# MTX_pic_piggyback_BRW_SOIC_V14.net
KiCad netlist of a schematic drawn in EAGLE
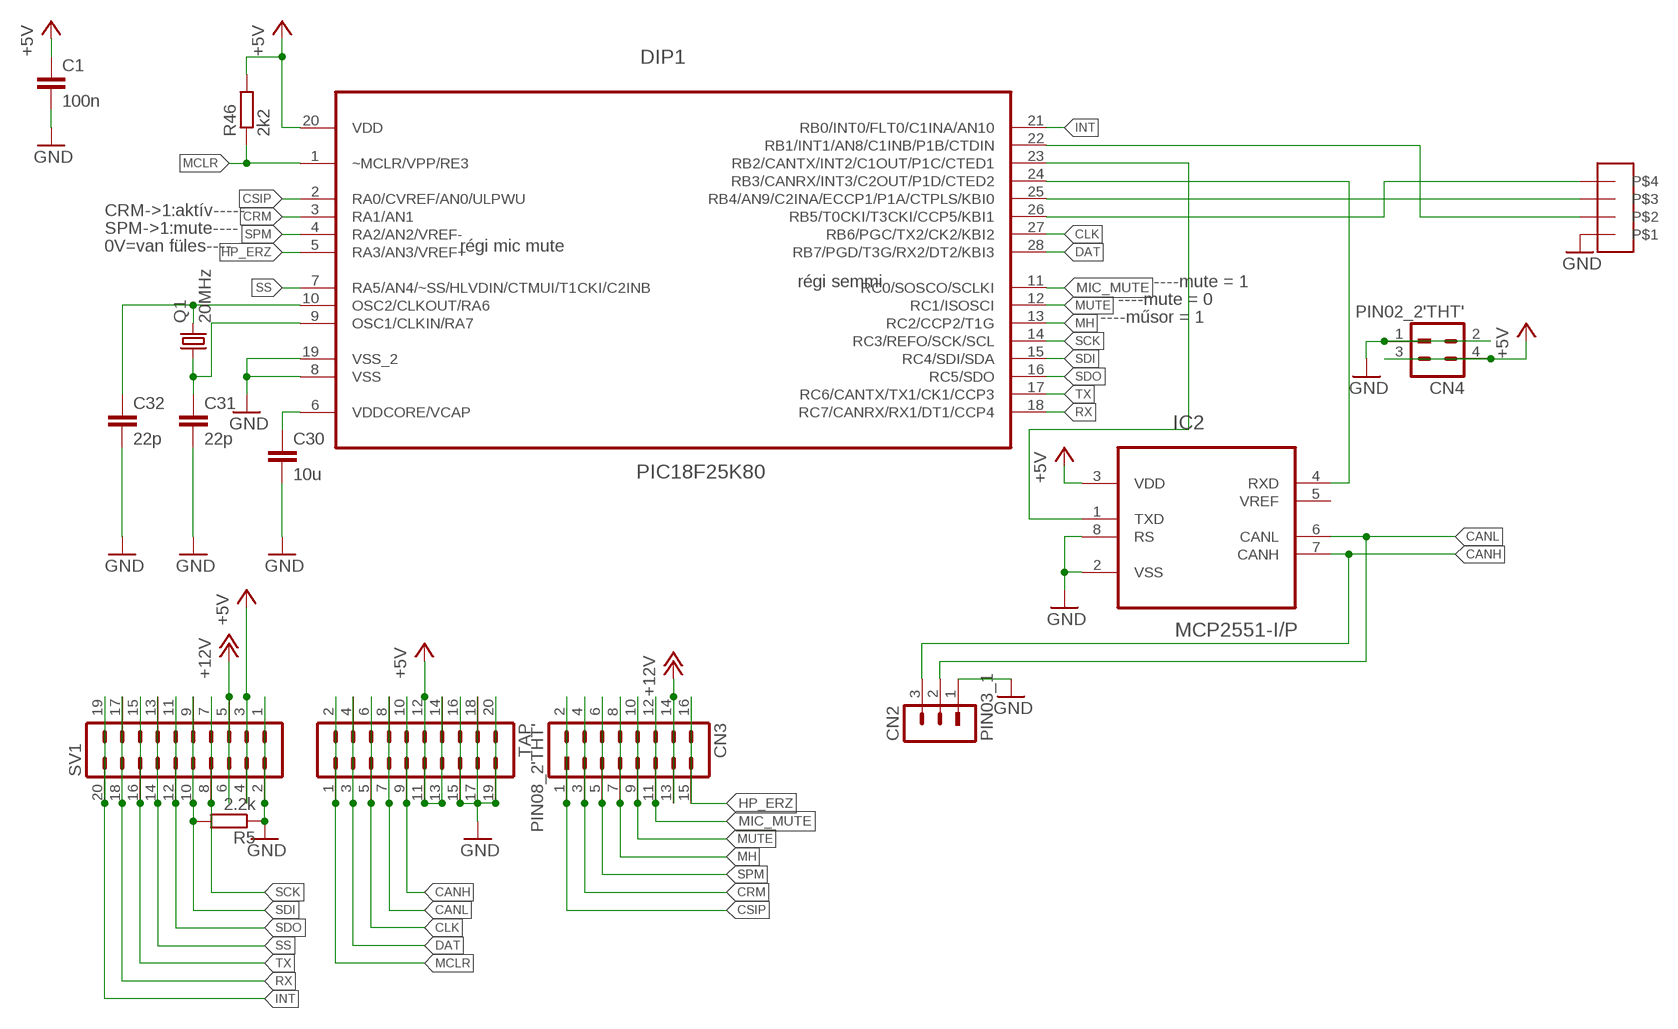
[diagram p0: schematic, sheet 1]

(export (version "E")
  (design (tool "Eeschema 10.0.6"))
  (components
    (comp (ref "C1")
      (value "100n")
      (footprint "eagle-import:C0805")
      (libsource (lib "eagle-import") (part "C-EUC0805"))
    )
    (comp (ref "C30")
      (value "10u")
      (footprint "eagle-import:C0805")
      (libsource (lib "eagle-import") (part "C-EUC0805"))
    )
    (comp (ref "C31")
      (value "22p")
      (footprint "eagle-import:C0805")
      (libsource (lib "eagle-import") (part "C-EUC0805"))
    )
    (comp (ref "C32")
      (value "22p")
      (footprint "eagle-import:C0805")
      (libsource (lib "eagle-import") (part "C-EUC0805"))
    )
    (comp (ref "CN2")
      (value "PIN03_1")
      (footprint "eagle-import:PIN03_1")
      (libsource (lib "eagle-import") (part "PIN03_1"))
    )
    (comp (ref "CN3")
      (value "PIN08_2'THT'")
      (footprint "eagle-import:PIN08_2")
      (libsource (lib "eagle-import") (part "PIN08_2'THT'"))
    )
    (comp (ref "CN4")
      (value "PIN02_2'THT'")
      (footprint "eagle-import:PIN02_2")
      (libsource (lib "eagle-import") (part "PIN02_2'THT'"))
    )
    (comp (ref "DIP1")
      (value "PIC18F25K80")
      (footprint "eagle-import:SOIC127P1030X265-28N")
      (libsource (lib "eagle-import") (part "PIC18F25K80"))
    )
    (comp (ref "IC2")
      (value "MCP2551-I/P")
      (footprint "eagle-import:DIP254P762X432-8")
      (libsource (lib "eagle-import") (part "MCP2551-I/P"))
    )
    (comp (ref "Q1")
      (value "20MHz")
      (footprint "eagle-import:XTAL_QS")
      (libsource (lib "eagle-import") (part "XTAL_2QS"))
    )
    (comp (ref "R5")
      (value "2.2k")
      (footprint "eagle-import:R0805")
      (libsource (lib "eagle-import") (part "R-EU_R0805"))
    )
    (comp (ref "R46")
      (value "2k2")
      (footprint "eagle-import:R0805")
      (libsource (lib "eagle-import") (part "R-EU_R0805"))
    )
    (comp (ref "SV1")
      (value "MA10-2")
      (footprint "eagle-import:MA10-2")
      (libsource (lib "eagle-import") (part "MA10-2"))
    )
    (comp (ref "TAP")
      (value "MA10-2")
      (footprint "eagle-import:MA10-2")
      (libsource (lib "eagle-import") (part "MA10-2"))
    )
    (comp (ref "U$1")
      (value "FEHER_TUS_4")
      (footprint "eagle-import:FEHER_TUS_4")
      (libsource (lib "eagle-import") (part "FEHER_TUS_4"))
    )
  )
  (nets
    (net (code "1") (name "+5V") (class "Default")
      (node (ref "C1") (pin "1") (pinfunction "1_1") (pintype "passive"))
      (node (ref "CN4") (pin "3") (pinfunction "3_3") (pintype "passive"))
      (node (ref "CN4") (pin "4") (pinfunction "4_4") (pintype "passive"))
      (node (ref "DIP1") (pin "20") (pinfunction "VDD_20") (pintype "power_in"))
      (node (ref "IC2") (pin "3") (pinfunction "VDD_3") (pintype "power_in"))
      (node (ref "R46") (pin "2") (pinfunction "2_2") (pintype "passive"))
      (node (ref "SV1") (pin "3") (pinfunction "3_3") (pintype "passive"))
      (node (ref "SV1") (pin "4") (pinfunction "4_4") (pintype "passive"))
      (node (ref "TAP") (pin "11") (pinfunction "11_11") (pintype "passive"))
      (node (ref "TAP") (pin "12") (pinfunction "12_12") (pintype "passive"))
      (node (ref "TAP") (pin "13") (pinfunction "13_13") (pintype "passive"))
      (node (ref "TAP") (pin "14") (pinfunction "14_14") (pintype "passive"))
    )
    (net (code "2") (name "+12V") (class "Default")
      (node (ref "CN3") (pin "13") (pinfunction "13_13") (pintype "passive"))
      (node (ref "CN3") (pin "14") (pinfunction "14_14") (pintype "passive"))
      (node (ref "SV1") (pin "5") (pinfunction "5_5") (pintype "passive"))
      (node (ref "SV1") (pin "6") (pinfunction "6_6") (pintype "passive"))
    )
    (net (code "3") (name "CANH") (class "Default")
      (node (ref "CN2") (pin "3") (pinfunction "3_3") (pintype "passive"))
      (node (ref "IC2") (pin "7") (pinfunction "CANH_7") (pintype "bidirectional"))
      (node (ref "TAP") (pin "10") (pinfunction "10_10") (pintype "passive"))
      (node (ref "TAP") (pin "9") (pinfunction "9_9") (pintype "passive"))
    )
    (net (code "4") (name "CANL") (class "Default")
      (node (ref "CN2") (pin "2") (pinfunction "2_2") (pintype "passive"))
      (node (ref "IC2") (pin "6") (pinfunction "CANL_6") (pintype "bidirectional"))
      (node (ref "TAP") (pin "7") (pinfunction "7_7") (pintype "passive"))
      (node (ref "TAP") (pin "8") (pinfunction "8_8") (pintype "passive"))
    )
    (net (code "5") (name "CLK") (class "Default")
      (node (ref "DIP1") (pin "27") (pinfunction "RB6/PGC/TX2/CK2/KBI2_27") (pintype "bidirectional"))
      (node (ref "TAP") (pin "5") (pinfunction "5_5") (pintype "passive"))
      (node (ref "TAP") (pin "6") (pinfunction "6_6") (pintype "passive"))
    )
    (net (code "6") (name "CRM") (class "Default")
      (node (ref "CN3") (pin "3") (pinfunction "3_3") (pintype "passive"))
      (node (ref "CN3") (pin "4") (pinfunction "4_4") (pintype "passive"))
      (node (ref "DIP1") (pin "3") (pinfunction "RA1/AN1_3") (pintype "bidirectional"))
    )
    (net (code "7") (name "CSIP") (class "Default")
      (node (ref "CN3") (pin "1") (pinfunction "1_1") (pintype "passive"))
      (node (ref "CN3") (pin "2") (pinfunction "2_2") (pintype "passive"))
      (node (ref "DIP1") (pin "2") (pinfunction "RA0/CVREF/AN0/ULPWU_2") (pintype "bidirectional"))
    )
    (net (code "8") (name "DAT") (class "Default")
      (node (ref "DIP1") (pin "28") (pinfunction "RB7/PGD/T3G/RX2/DT2/KBI3_28") (pintype "bidirectional"))
      (node (ref "TAP") (pin "3") (pinfunction "3_3") (pintype "passive"))
      (node (ref "TAP") (pin "4") (pinfunction "4_4") (pintype "passive"))
    )
    (net (code "9") (name "GND") (class "Default")
      (node (ref "C1") (pin "2") (pinfunction "2_2") (pintype "passive"))
      (node (ref "C30") (pin "2") (pinfunction "2_2") (pintype "passive"))
      (node (ref "C31") (pin "2") (pinfunction "2_2") (pintype "passive"))
      (node (ref "C32") (pin "2") (pinfunction "2_2") (pintype "passive"))
      (node (ref "CN2") (pin "1") (pinfunction "1_1") (pintype "passive"))
      (node (ref "CN4") (pin "1") (pinfunction "1_1") (pintype "passive"))
      (node (ref "CN4") (pin "2") (pinfunction "2_2") (pintype "passive"))
      (node (ref "DIP1") (pin "19") (pinfunction "VSS_2_19") (pintype "power_in"))
      (node (ref "DIP1") (pin "8") (pinfunction "VSS_8") (pintype "power_in"))
      (node (ref "IC2") (pin "2") (pinfunction "VSS_2") (pintype "power_in"))
      (node (ref "IC2") (pin "8") (pinfunction "RS_8") (pintype "input"))
      (node (ref "R5") (pin "1") (pinfunction "1_1") (pintype "passive"))
      (node (ref "SV1") (pin "1") (pinfunction "1_1") (pintype "passive"))
      (node (ref "SV1") (pin "2") (pinfunction "2_2") (pintype "passive"))
      (node (ref "TAP") (pin "15") (pinfunction "15_15") (pintype "passive"))
      (node (ref "TAP") (pin "16") (pinfunction "16_16") (pintype "passive"))
      (node (ref "TAP") (pin "17") (pinfunction "17_17") (pintype "passive"))
      (node (ref "TAP") (pin "18") (pinfunction "18_18") (pintype "passive"))
      (node (ref "TAP") (pin "19") (pinfunction "19_19") (pintype "passive"))
      (node (ref "TAP") (pin "20") (pinfunction "20_20") (pintype "passive"))
      (node (ref "U$1") (pin "P$1") (pinfunction "P$1_P$1") (pintype "bidirectional"))
    )
    (net (code "10") (name "HP_ERZ") (class "Default")
      (node (ref "CN3") (pin "15") (pinfunction "15_15") (pintype "passive"))
      (node (ref "CN3") (pin "16") (pinfunction "16_16") (pintype "passive"))
      (node (ref "DIP1") (pin "5") (pinfunction "RA3/AN3/VREF+_5") (pintype "bidirectional"))
    )
    (net (code "11") (name "INT") (class "Default")
      (node (ref "DIP1") (pin "21") (pinfunction "RB0/INT0/FLT0/C1INA/AN10_21") (pintype "bidirectional"))
      (node (ref "SV1") (pin "19") (pinfunction "19_19") (pintype "passive"))
      (node (ref "SV1") (pin "20") (pinfunction "20_20") (pintype "passive"))
    )
    (net (code "12") (name "MCLR") (class "Default")
      (node (ref "DIP1") (pin "1") (pinfunction "~{MCLR/VPP/RE3}_1") (pintype "input"))
      (node (ref "R46") (pin "1") (pinfunction "1_1") (pintype "passive"))
      (node (ref "TAP") (pin "1") (pinfunction "1_1") (pintype "passive"))
      (node (ref "TAP") (pin "2") (pinfunction "2_2") (pintype "passive"))
    )
    (net (code "13") (name "MH") (class "Default")
      (node (ref "CN3") (pin "7") (pinfunction "7_7") (pintype "passive"))
      (node (ref "CN3") (pin "8") (pinfunction "8_8") (pintype "passive"))
      (node (ref "DIP1") (pin "13") (pinfunction "RC2/CCP2/T1G_13") (pintype "bidirectional"))
    )
    (net (code "14") (name "MIC_MUTE") (class "Default")
      (node (ref "CN3") (pin "11") (pinfunction "11_11") (pintype "passive"))
      (node (ref "CN3") (pin "12") (pinfunction "12_12") (pintype "passive"))
      (node (ref "DIP1") (pin "11") (pinfunction "RC0/SOSCO/SCLKI_11") (pintype "bidirectional"))
    )
    (net (code "15") (name "MUTE") (class "Default")
      (node (ref "CN3") (pin "10") (pinfunction "10_10") (pintype "passive"))
      (node (ref "CN3") (pin "9") (pinfunction "9_9") (pintype "passive"))
      (node (ref "DIP1") (pin "12") (pinfunction "RC1/ISOSCI_12") (pintype "bidirectional"))
    )
    (net (code "16") (name "Net-(DIP1-OSC1{slash}CLKIN{slash}RA7)") (class "Default")
      (node (ref "C31") (pin "1") (pinfunction "1_1") (pintype "passive"))
      (node (ref "DIP1") (pin "9") (pinfunction "OSC1/CLKIN/RA7_9") (pintype "bidirectional"))
      (node (ref "Q1") (pin "1") (pinfunction "1_1") (pintype "passive"))
    )
    (net (code "17") (name "Net-(DIP1-OSC2{slash}CLKOUT{slash}RA6)") (class "Default")
      (node (ref "C32") (pin "1") (pinfunction "1_1") (pintype "passive"))
      (node (ref "DIP1") (pin "10") (pinfunction "OSC2/CLKOUT/RA6_10") (pintype "bidirectional"))
      (node (ref "Q1") (pin "2") (pinfunction "2_2") (pintype "passive"))
    )
    (net (code "18") (name "Net-(DIP1-RB1{slash}INT1{slash}AN8{slash}C1INB{slash}P1B{slash}CTDIN)") (class "Default")
      (node (ref "DIP1") (pin "22") (pinfunction "RB1/INT1/AN8/C1INB/P1B/CTDIN_22") (pintype "bidirectional"))
      (node (ref "U$1") (pin "P$2") (pinfunction "P$2_P$2") (pintype "bidirectional"))
    )
    (net (code "19") (name "Net-(DIP1-RB2{slash}CANTX{slash}INT2{slash}C1OUT{slash}P1C{slash}CTED1)") (class "Default")
      (node (ref "DIP1") (pin "23") (pinfunction "RB2/CANTX/INT2/C1OUT/P1C/CTED1_23") (pintype "bidirectional"))
      (node (ref "IC2") (pin "1") (pinfunction "TXD_1") (pintype "input"))
    )
    (net (code "20") (name "Net-(DIP1-RB3{slash}CANRX{slash}INT3{slash}C2OUT{slash}P1D{slash}CTED2)") (class "Default")
      (node (ref "DIP1") (pin "24") (pinfunction "RB3/CANRX/INT3/C2OUT/P1D/CTED2_24") (pintype "bidirectional"))
      (node (ref "IC2") (pin "4") (pinfunction "RXD_4") (pintype "output"))
    )
    (net (code "21") (name "Net-(DIP1-RB4{slash}AN9{slash}C2INA{slash}ECCP1{slash}P1A{slash}CTPLS{slash}KBI0)") (class "Default")
      (node (ref "DIP1") (pin "25") (pinfunction "RB4/AN9/C2INA/ECCP1/P1A/CTPLS/KBI0_25") (pintype "bidirectional"))
      (node (ref "U$1") (pin "P$3") (pinfunction "P$3_P$3") (pintype "bidirectional"))
    )
    (net (code "22") (name "Net-(DIP1-RB5{slash}T0CKI{slash}T3CKI{slash}CCP5{slash}KBI1)") (class "Default")
      (node (ref "DIP1") (pin "26") (pinfunction "RB5/T0CKI/T3CKI/CCP5/KBI1_26") (pintype "bidirectional"))
      (node (ref "U$1") (pin "P$4") (pinfunction "P$4_P$4") (pintype "bidirectional"))
    )
    (net (code "23") (name "Net-(DIP1-VDDCORE{slash}VCAP)") (class "Default")
      (node (ref "C30") (pin "1") (pinfunction "1_1") (pintype "passive"))
      (node (ref "DIP1") (pin "6") (pinfunction "VDDCORE/VCAP_6") (pintype "bidirectional"))
    )
    (net (code "24") (name "RX") (class "Default")
      (node (ref "DIP1") (pin "18") (pinfunction "RC7/CANRX/RX1/DT1/CCP4_18") (pintype "bidirectional"))
      (node (ref "SV1") (pin "17") (pinfunction "17_17") (pintype "passive"))
      (node (ref "SV1") (pin "18") (pinfunction "18_18") (pintype "passive"))
    )
    (net (code "25") (name "SCK") (class "Default")
      (node (ref "DIP1") (pin "14") (pinfunction "RC3/REFO/SCK/SCL_14") (pintype "bidirectional"))
      (node (ref "SV1") (pin "7") (pinfunction "7_7") (pintype "passive"))
      (node (ref "SV1") (pin "8") (pinfunction "8_8") (pintype "passive"))
    )
    (net (code "26") (name "SDI") (class "Default")
      (node (ref "DIP1") (pin "15") (pinfunction "RC4/SDI/SDA_15") (pintype "bidirectional"))
      (node (ref "R5") (pin "2") (pinfunction "2_2") (pintype "passive"))
      (node (ref "SV1") (pin "10") (pinfunction "10_10") (pintype "passive"))
      (node (ref "SV1") (pin "9") (pinfunction "9_9") (pintype "passive"))
    )
    (net (code "27") (name "SDO") (class "Default")
      (node (ref "DIP1") (pin "16") (pinfunction "RC5/SDO_16") (pintype "bidirectional"))
      (node (ref "SV1") (pin "11") (pinfunction "11_11") (pintype "passive"))
      (node (ref "SV1") (pin "12") (pinfunction "12_12") (pintype "passive"))
    )
    (net (code "28") (name "SPM") (class "Default")
      (node (ref "CN3") (pin "5") (pinfunction "5_5") (pintype "passive"))
      (node (ref "CN3") (pin "6") (pinfunction "6_6") (pintype "passive"))
      (node (ref "DIP1") (pin "4") (pinfunction "RA2/AN2/VREF-_4") (pintype "bidirectional"))
    )
    (net (code "29") (name "SS") (class "Default")
      (node (ref "DIP1") (pin "7") (pinfunction "RA5/AN4/~{SS/HLVDIN/CTMUI/T1CKI/C2INB}_7") (pintype "bidirectional"))
      (node (ref "SV1") (pin "13") (pinfunction "13_13") (pintype "passive"))
      (node (ref "SV1") (pin "14") (pinfunction "14_14") (pintype "passive"))
    )
    (net (code "30") (name "TX") (class "Default")
      (node (ref "DIP1") (pin "17") (pinfunction "RC6/CANTX/TX1/CK1/CCP3_17") (pintype "bidirectional"))
      (node (ref "SV1") (pin "15") (pinfunction "15_15") (pintype "passive"))
      (node (ref "SV1") (pin "16") (pinfunction "16_16") (pintype "passive"))
    )
    (net (code "31") (name "unconnected-(IC2-VREF-Pad5)") (class "Default")
      (node (ref "IC2") (pin "5") (pinfunction "VREF_5") (pintype "output"))
    )
  )
)
